# LightADC.net
KiCad netlist of a schematic drawn in Altium Designer
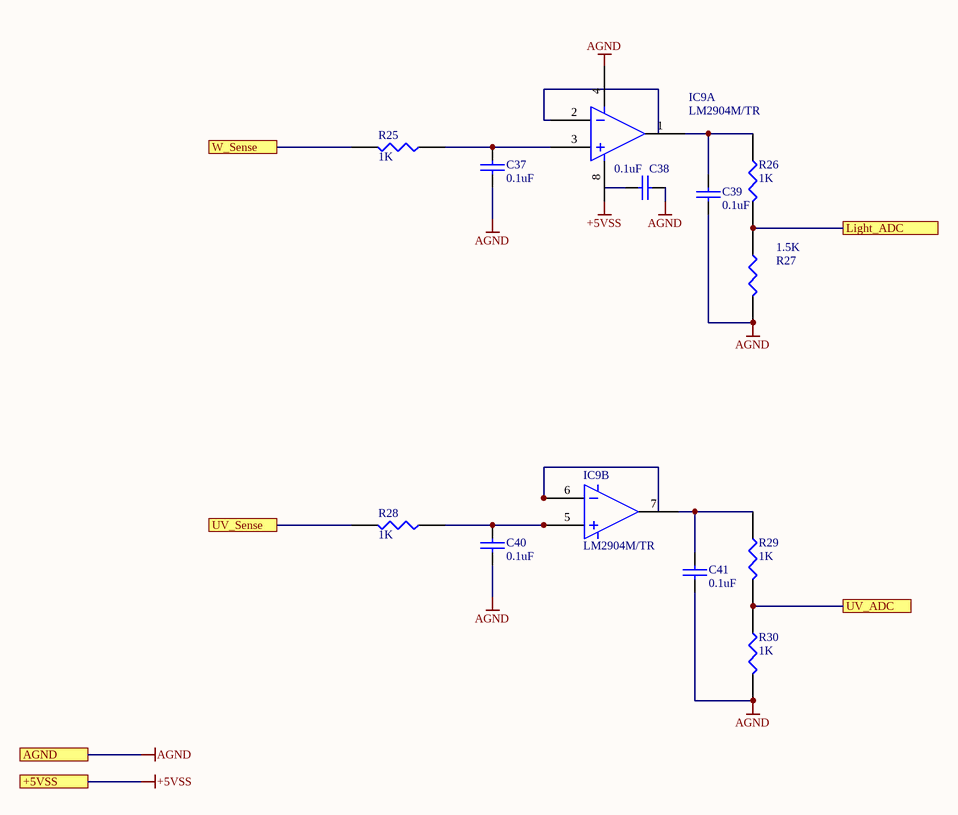
[diagram p0: LightADC.SchDoc]

(export (version "E")
  (design (tool "Eeschema 10.0.6"))
  (components
    (comp (ref "C37")
      (value "0.1uF")
      (footprint "0805C")
      (description "Capacitor")
      (libsource (lib "*") (part "CAP"))
    )
    (comp (ref "C38")
      (value "0.1uF")
      (footprint "0603C")
      (description "Capacitor")
      (libsource (lib "*") (part "CAP"))
    )
    (comp (ref "C39")
      (value "0.1uF")
      (footprint "0603C")
      (description "Capacitor")
      (libsource (lib "*") (part "CAP"))
    )
    (comp (ref "C40")
      (value "0.1uF")
      (footprint "0805C")
      (description "Capacitor")
      (libsource (lib "*") (part "CAP"))
    )
    (comp (ref "C41")
      (value "0.1uF")
      (footprint "0805C")
      (description "Capacitor")
      (libsource (lib "*") (part "CAP"))
    )
    (comp (ref "IC9")
      (value "LM2904M/TR")
      (footprint "LM2904M/TR")
      (libsource (lib "main board fo stk_1") (part "TL072"))
    )
    (comp (ref "R25") (value "1K") (footprint "0805R") (libsource (lib "*") (part "RES1")))
    (comp (ref "R26") (value "1K") (footprint "0805R") (libsource (lib "*") (part "RES1")))
    (comp (ref "R27") (value "1.5K") (footprint "0805R") (libsource (lib "*") (part "RES1")))
    (comp (ref "R28") (value "1K") (footprint "0805R") (libsource (lib "*") (part "RES1")))
    (comp (ref "R29") (value "1K") (footprint "0805R") (libsource (lib "*") (part "RES1")))
    (comp (ref "R30") (value "1K") (footprint "0805R") (libsource (lib "*") (part "RES1")))
  )
  (nets
    (net (code "1") (name "+5VSS") (class "Default") (node (ref "IC9") (pin "8") (pintype "passive")))
    (net (code "2") (name "/Light_ADC") (class "Default")
      (node (ref "R26") (pin "2") (pinfunction "2_2") (pintype "passive"))
      (node (ref "R27") (pin "1") (pinfunction "1_1") (pintype "passive"))
    )
    (net (code "3") (name "/UV_ADC") (class "Default")
      (node (ref "R29") (pin "2") (pinfunction "2_2") (pintype "passive"))
      (node (ref "R30") (pin "1") (pinfunction "1_1") (pintype "passive"))
    )
    (net (code "4") (name "/UV_Sense") (class "Default")
      (node (ref "R28") (pin "2") (pinfunction "2_2") (pintype "passive"))
    )
    (net (code "5") (name "/W_Sense") (class "Default")
      (node (ref "R25") (pin "2") (pinfunction "2_2") (pintype "passive"))
    )
    (net (code "6") (name "AGND") (class "Default")
      (node (ref "C37") (pin "2") (pinfunction "2_2") (pintype "passive"))
      (node (ref "C38") (pin "1") (pinfunction "1_1") (pintype "passive"))
      (node (ref "C39") (pin "2") (pinfunction "2_2") (pintype "passive"))
      (node (ref "C40") (pin "2") (pinfunction "2_2") (pintype "passive"))
      (node (ref "C41") (pin "2") (pinfunction "2_2") (pintype "passive"))
      (node (ref "R27") (pin "2") (pinfunction "2_2") (pintype "passive"))
      (node (ref "R30") (pin "2") (pinfunction "2_2") (pintype "passive"))
    )
    (net (code "7") (name "Net-(C37-Pad1)") (class "Default")
      (node (ref "C37") (pin "1") (pinfunction "1_1") (pintype "passive"))
      (node (ref "IC9") (pin "3") (pintype "passive"))
      (node (ref "R25") (pin "1") (pinfunction "1_1") (pintype "passive"))
    )
    (net (code "8") (name "Net-(C39-Pad1)") (class "Default")
      (node (ref "C39") (pin "1") (pinfunction "1_1") (pintype "passive"))
      (node (ref "IC9") (pin "1") (pintype "passive"))
      (node (ref "R26") (pin "1") (pinfunction "1_1") (pintype "passive"))
    )
    (net (code "9") (name "Net-(C40-Pad1)") (class "Default")
      (node (ref "C40") (pin "1") (pinfunction "1_1") (pintype "passive"))
      (node (ref "IC9") (pin "5") (pintype "passive"))
      (node (ref "R28") (pin "1") (pinfunction "1_1") (pintype "passive"))
    )
    (net (code "10") (name "Net-(C41-Pad1)") (class "Default")
      (node (ref "C41") (pin "1") (pinfunction "1_1") (pintype "passive"))
      (node (ref "IC9") (pin "7") (pintype "passive"))
      (node (ref "R29") (pin "1") (pinfunction "1_1") (pintype "passive"))
    )
    (net (code "11") (name "unconnected-(C38-Pad2)") (class "Default")
      (node (ref "C38") (pin "2") (pinfunction "2_2") (pintype "passive"))
    )
    (net (code "12") (name "unconnected-(IC9-Pad2)") (class "Default")
      (node (ref "IC9") (pin "2") (pintype "passive"))
    )
    (net (code "13") (name "unconnected-(IC9-Pad4)") (class "Default")
      (node (ref "IC9") (pin "4") (pintype "passive"))
    )
    (net (code "14") (name "unconnected-(IC9-Pad6)") (class "Default")
      (node (ref "IC9") (pin "6") (pintype "passive"))
    )
  )
)
